# MCU_GPIO.net
KiCad netlist of a schematic drawn in Altium Designer
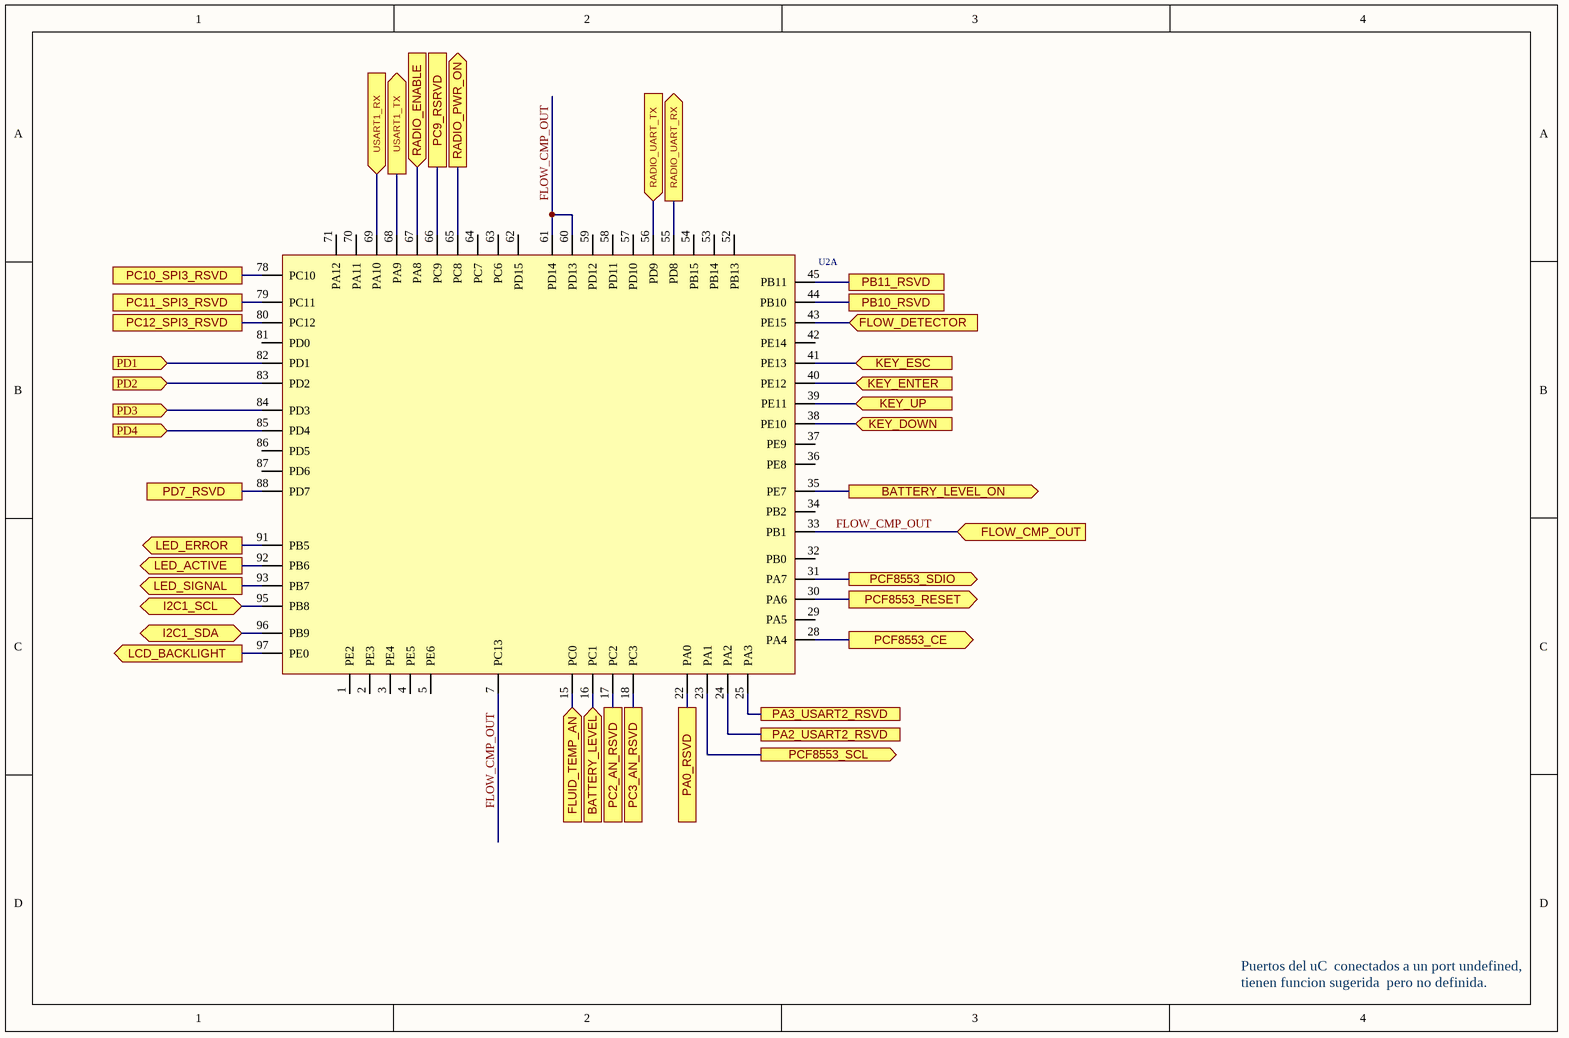
[diagram p0: MCU_GPIO.SchDoc]

(export (version "E")
  (design (tool "Eeschema 10.0.6"))
  (components
    (comp (ref "U2")
      (value "STM32U575VIT6Q")
      (footprint "STM32U575VI")
      (fields (field (name "MANUFACTURER") "ST"))
      (libsource (lib "flowmeet") (part "STM32U575VIT6Q"))
    )
  )
  (nets
    (net (code "1") (name "/BATTERY_LEVEL") (class "Default")
      (node (ref "U2") (pin "16") (pinfunction "PC1_16") (pintype "passive"))
    )
    (net (code "2") (name "/BATTERY_LEVEL_ON") (class "Default")
      (node (ref "U2") (pin "35") (pinfunction "PE7_35") (pintype "passive"))
    )
    (net (code "3") (name "/FLOW_CMP_OUT") (class "Default")
      (node (ref "U2") (pin "33") (pinfunction "PB1_33") (pintype "passive"))
      (node (ref "U2") (pin "60") (pinfunction "PD13_60") (pintype "passive"))
      (node (ref "U2") (pin "61") (pinfunction "PD14_61") (pintype "passive"))
      (node (ref "U2") (pin "7") (pinfunction "PC13_7") (pintype "passive"))
    )
    (net (code "4") (name "/FLOW_DETECTOR") (class "Default")
      (node (ref "U2") (pin "43") (pinfunction "PE15_43") (pintype "passive"))
    )
    (net (code "5") (name "/FLUID_TEMP_AN") (class "Default")
      (node (ref "U2") (pin "15") (pinfunction "PC0_15") (pintype "passive"))
    )
    (net (code "6") (name "/I2C1_SCL") (class "Default")
      (node (ref "U2") (pin "95") (pinfunction "PB8_95") (pintype "passive"))
    )
    (net (code "7") (name "/I2C1_SDA") (class "Default")
      (node (ref "U2") (pin "96") (pinfunction "PB9_96") (pintype "passive"))
    )
    (net (code "8") (name "/KEY_DOWN") (class "Default")
      (node (ref "U2") (pin "38") (pinfunction "PE10_38") (pintype "passive"))
    )
    (net (code "9") (name "/KEY_ENTER") (class "Default")
      (node (ref "U2") (pin "40") (pinfunction "PE12_40") (pintype "passive"))
    )
    (net (code "10") (name "/KEY_ESC") (class "Default")
      (node (ref "U2") (pin "41") (pinfunction "PE13_41") (pintype "passive"))
    )
    (net (code "11") (name "/KEY_UP") (class "Default")
      (node (ref "U2") (pin "39") (pinfunction "PE11_39") (pintype "passive"))
    )
    (net (code "12") (name "/LCD_BACKLIGHT") (class "Default")
      (node (ref "U2") (pin "97") (pinfunction "PE0_97") (pintype "passive"))
    )
    (net (code "13") (name "/LED_ACTIVE") (class "Default")
      (node (ref "U2") (pin "92") (pinfunction "PB6_92") (pintype "passive"))
    )
    (net (code "14") (name "/LED_ERROR") (class "Default")
      (node (ref "U2") (pin "91") (pinfunction "PB5_91") (pintype "passive"))
    )
    (net (code "15") (name "/LED_SIGNAL") (class "Default")
      (node (ref "U2") (pin "93") (pinfunction "PB7_93") (pintype "passive"))
    )
    (net (code "16") (name "/PA0_RSVD") (class "Default")
      (node (ref "U2") (pin "22") (pinfunction "PA0_22") (pintype "passive"))
    )
    (net (code "17") (name "/PA2_USART2_RSVD") (class "Default")
      (node (ref "U2") (pin "24") (pinfunction "PA2_24") (pintype "passive"))
    )
    (net (code "18") (name "/PA3_USART2_RSVD") (class "Default")
      (node (ref "U2") (pin "25") (pinfunction "PA3_25") (pintype "passive"))
    )
    (net (code "19") (name "/PB10_RSVD") (class "Default")
      (node (ref "U2") (pin "44") (pinfunction "PB10_44") (pintype "passive"))
    )
    (net (code "20") (name "/PB11_RSVD") (class "Default")
      (node (ref "U2") (pin "45") (pinfunction "PB11_45") (pintype "passive"))
    )
    (net (code "21") (name "/PC2_AN_RSVD") (class "Default")
      (node (ref "U2") (pin "17") (pinfunction "PC2_17") (pintype "passive"))
    )
    (net (code "22") (name "/PC3_AN_RSVD") (class "Default")
      (node (ref "U2") (pin "18") (pinfunction "PC3_18") (pintype "passive"))
    )
    (net (code "23") (name "/PC9_RSRVD") (class "Default")
      (node (ref "U2") (pin "66") (pinfunction "PC9_66") (pintype "passive"))
    )
    (net (code "24") (name "/PC10_SPI3_RSVD") (class "Default")
      (node (ref "U2") (pin "78") (pinfunction "PC10_78") (pintype "passive"))
    )
    (net (code "25") (name "/PC11_SPI3_RSVD") (class "Default")
      (node (ref "U2") (pin "79") (pinfunction "PC11_79") (pintype "passive"))
    )
    (net (code "26") (name "/PC12_SPI3_RSVD") (class "Default")
      (node (ref "U2") (pin "80") (pinfunction "PC12_80") (pintype "passive"))
    )
    (net (code "27") (name "/PCF8553_CE") (class "Default")
      (node (ref "U2") (pin "28") (pinfunction "PA4_28") (pintype "passive"))
    )
    (net (code "28") (name "/PCF8553_RESET") (class "Default")
      (node (ref "U2") (pin "30") (pinfunction "PA6_30") (pintype "passive"))
    )
    (net (code "29") (name "/PCF8553_SCL") (class "Default")
      (node (ref "U2") (pin "23") (pinfunction "PA1_23") (pintype "passive"))
    )
    (net (code "30") (name "/PCF8553_SDIO") (class "Default")
      (node (ref "U2") (pin "31") (pinfunction "PA7_31") (pintype "passive"))
    )
    (net (code "31") (name "/PD1") (class "Default")
      (node (ref "U2") (pin "82") (pinfunction "PD1_82") (pintype "passive"))
    )
    (net (code "32") (name "/PD2") (class "Default")
      (node (ref "U2") (pin "83") (pinfunction "PD2_83") (pintype "passive"))
    )
    (net (code "33") (name "/PD3") (class "Default")
      (node (ref "U2") (pin "84") (pinfunction "PD3_84") (pintype "passive"))
    )
    (net (code "34") (name "/PD4") (class "Default")
      (node (ref "U2") (pin "85") (pinfunction "PD4_85") (pintype "passive"))
    )
    (net (code "35") (name "/PD7_RSVD") (class "Default")
      (node (ref "U2") (pin "88") (pinfunction "PD7_88") (pintype "passive"))
    )
    (net (code "36") (name "/RADIO_ENABLE") (class "Default")
      (node (ref "U2") (pin "67") (pinfunction "PA8_67") (pintype "passive"))
    )
    (net (code "37") (name "/RADIO_PWR_ON") (class "Default")
      (node (ref "U2") (pin "65") (pinfunction "PC8_65") (pintype "passive"))
    )
    (net (code "38") (name "/RADIO_UART_RX") (class "Default")
      (node (ref "U2") (pin "55") (pinfunction "PD8_55") (pintype "passive"))
    )
    (net (code "39") (name "/RADIO_UART_TX") (class "Default")
      (node (ref "U2") (pin "56") (pinfunction "PD9_56") (pintype "passive"))
    )
    (net (code "40") (name "/USART1_RX") (class "Default")
      (node (ref "U2") (pin "69") (pinfunction "PA10_69") (pintype "passive"))
    )
    (net (code "41") (name "/USART1_TX") (class "Default")
      (node (ref "U2") (pin "68") (pinfunction "PA9_68") (pintype "passive"))
    )
    (net (code "42") (name "unconnected-(U2A-PA5-Pad29)") (class "Default")
      (node (ref "U2") (pin "29") (pinfunction "PA5_29") (pintype "passive"))
    )
    (net (code "43") (name "unconnected-(U2A-PA11-Pad70)") (class "Default")
      (node (ref "U2") (pin "70") (pinfunction "PA11_70") (pintype "passive"))
    )
    (net (code "44") (name "unconnected-(U2A-PA12-Pad71)") (class "Default")
      (node (ref "U2") (pin "71") (pinfunction "PA12_71") (pintype "passive"))
    )
    (net (code "45") (name "unconnected-(U2A-PB0-Pad32)") (class "Default")
      (node (ref "U2") (pin "32") (pinfunction "PB0_32") (pintype "passive"))
    )
    (net (code "46") (name "unconnected-(U2A-PB2-Pad34)") (class "Default")
      (node (ref "U2") (pin "34") (pinfunction "PB2_34") (pintype "passive"))
    )
    (net (code "47") (name "unconnected-(U2A-PB13-Pad52)") (class "Default")
      (node (ref "U2") (pin "52") (pinfunction "PB13_52") (pintype "passive"))
    )
    (net (code "48") (name "unconnected-(U2A-PB14-Pad53)") (class "Default")
      (node (ref "U2") (pin "53") (pinfunction "PB14_53") (pintype "passive"))
    )
    (net (code "49") (name "unconnected-(U2A-PB15-Pad54)") (class "Default")
      (node (ref "U2") (pin "54") (pinfunction "PB15_54") (pintype "passive"))
    )
    (net (code "50") (name "unconnected-(U2A-PC6-Pad63)") (class "Default")
      (node (ref "U2") (pin "63") (pinfunction "PC6_63") (pintype "passive"))
    )
    (net (code "51") (name "unconnected-(U2A-PC7-Pad64)") (class "Default")
      (node (ref "U2") (pin "64") (pinfunction "PC7_64") (pintype "passive"))
    )
    (net (code "52") (name "unconnected-(U2A-PD0-Pad81)") (class "Default")
      (node (ref "U2") (pin "81") (pinfunction "PD0_81") (pintype "passive"))
    )
    (net (code "53") (name "unconnected-(U2A-PD5-Pad86)") (class "Default")
      (node (ref "U2") (pin "86") (pinfunction "PD5_86") (pintype "passive"))
    )
    (net (code "54") (name "unconnected-(U2A-PD6-Pad87)") (class "Default")
      (node (ref "U2") (pin "87") (pinfunction "PD6_87") (pintype "passive"))
    )
    (net (code "55") (name "unconnected-(U2A-PD10-Pad57)") (class "Default")
      (node (ref "U2") (pin "57") (pinfunction "PD10_57") (pintype "passive"))
    )
    (net (code "56") (name "unconnected-(U2A-PD11-Pad58)") (class "Default")
      (node (ref "U2") (pin "58") (pinfunction "PD11_58") (pintype "passive"))
    )
    (net (code "57") (name "unconnected-(U2A-PD12-Pad59)") (class "Default")
      (node (ref "U2") (pin "59") (pinfunction "PD12_59") (pintype "passive"))
    )
    (net (code "58") (name "unconnected-(U2A-PD15-Pad62)") (class "Default")
      (node (ref "U2") (pin "62") (pinfunction "PD15_62") (pintype "passive"))
    )
    (net (code "59") (name "unconnected-(U2A-PE2-Pad1)") (class "Default")
      (node (ref "U2") (pin "1") (pinfunction "PE2_1") (pintype "passive"))
    )
    (net (code "60") (name "unconnected-(U2A-PE3-Pad2)") (class "Default")
      (node (ref "U2") (pin "2") (pinfunction "PE3_2") (pintype "passive"))
    )
    (net (code "61") (name "unconnected-(U2A-PE4-Pad3)") (class "Default")
      (node (ref "U2") (pin "3") (pinfunction "PE4_3") (pintype "passive"))
    )
    (net (code "62") (name "unconnected-(U2A-PE5-Pad4)") (class "Default")
      (node (ref "U2") (pin "4") (pinfunction "PE5_4") (pintype "passive"))
    )
    (net (code "63") (name "unconnected-(U2A-PE6-Pad5)") (class "Default")
      (node (ref "U2") (pin "5") (pinfunction "PE6_5") (pintype "passive"))
    )
    (net (code "64") (name "unconnected-(U2A-PE8-Pad36)") (class "Default")
      (node (ref "U2") (pin "36") (pinfunction "PE8_36") (pintype "passive"))
    )
    (net (code "65") (name "unconnected-(U2A-PE9-Pad37)") (class "Default")
      (node (ref "U2") (pin "37") (pinfunction "PE9_37") (pintype "passive"))
    )
    (net (code "66") (name "unconnected-(U2A-PE14-Pad42)") (class "Default")
      (node (ref "U2") (pin "42") (pinfunction "PE14_42") (pintype "passive"))
    )
  )
)
